# Controller.net
KiCad netlist of a schematic drawn in Altium Designer
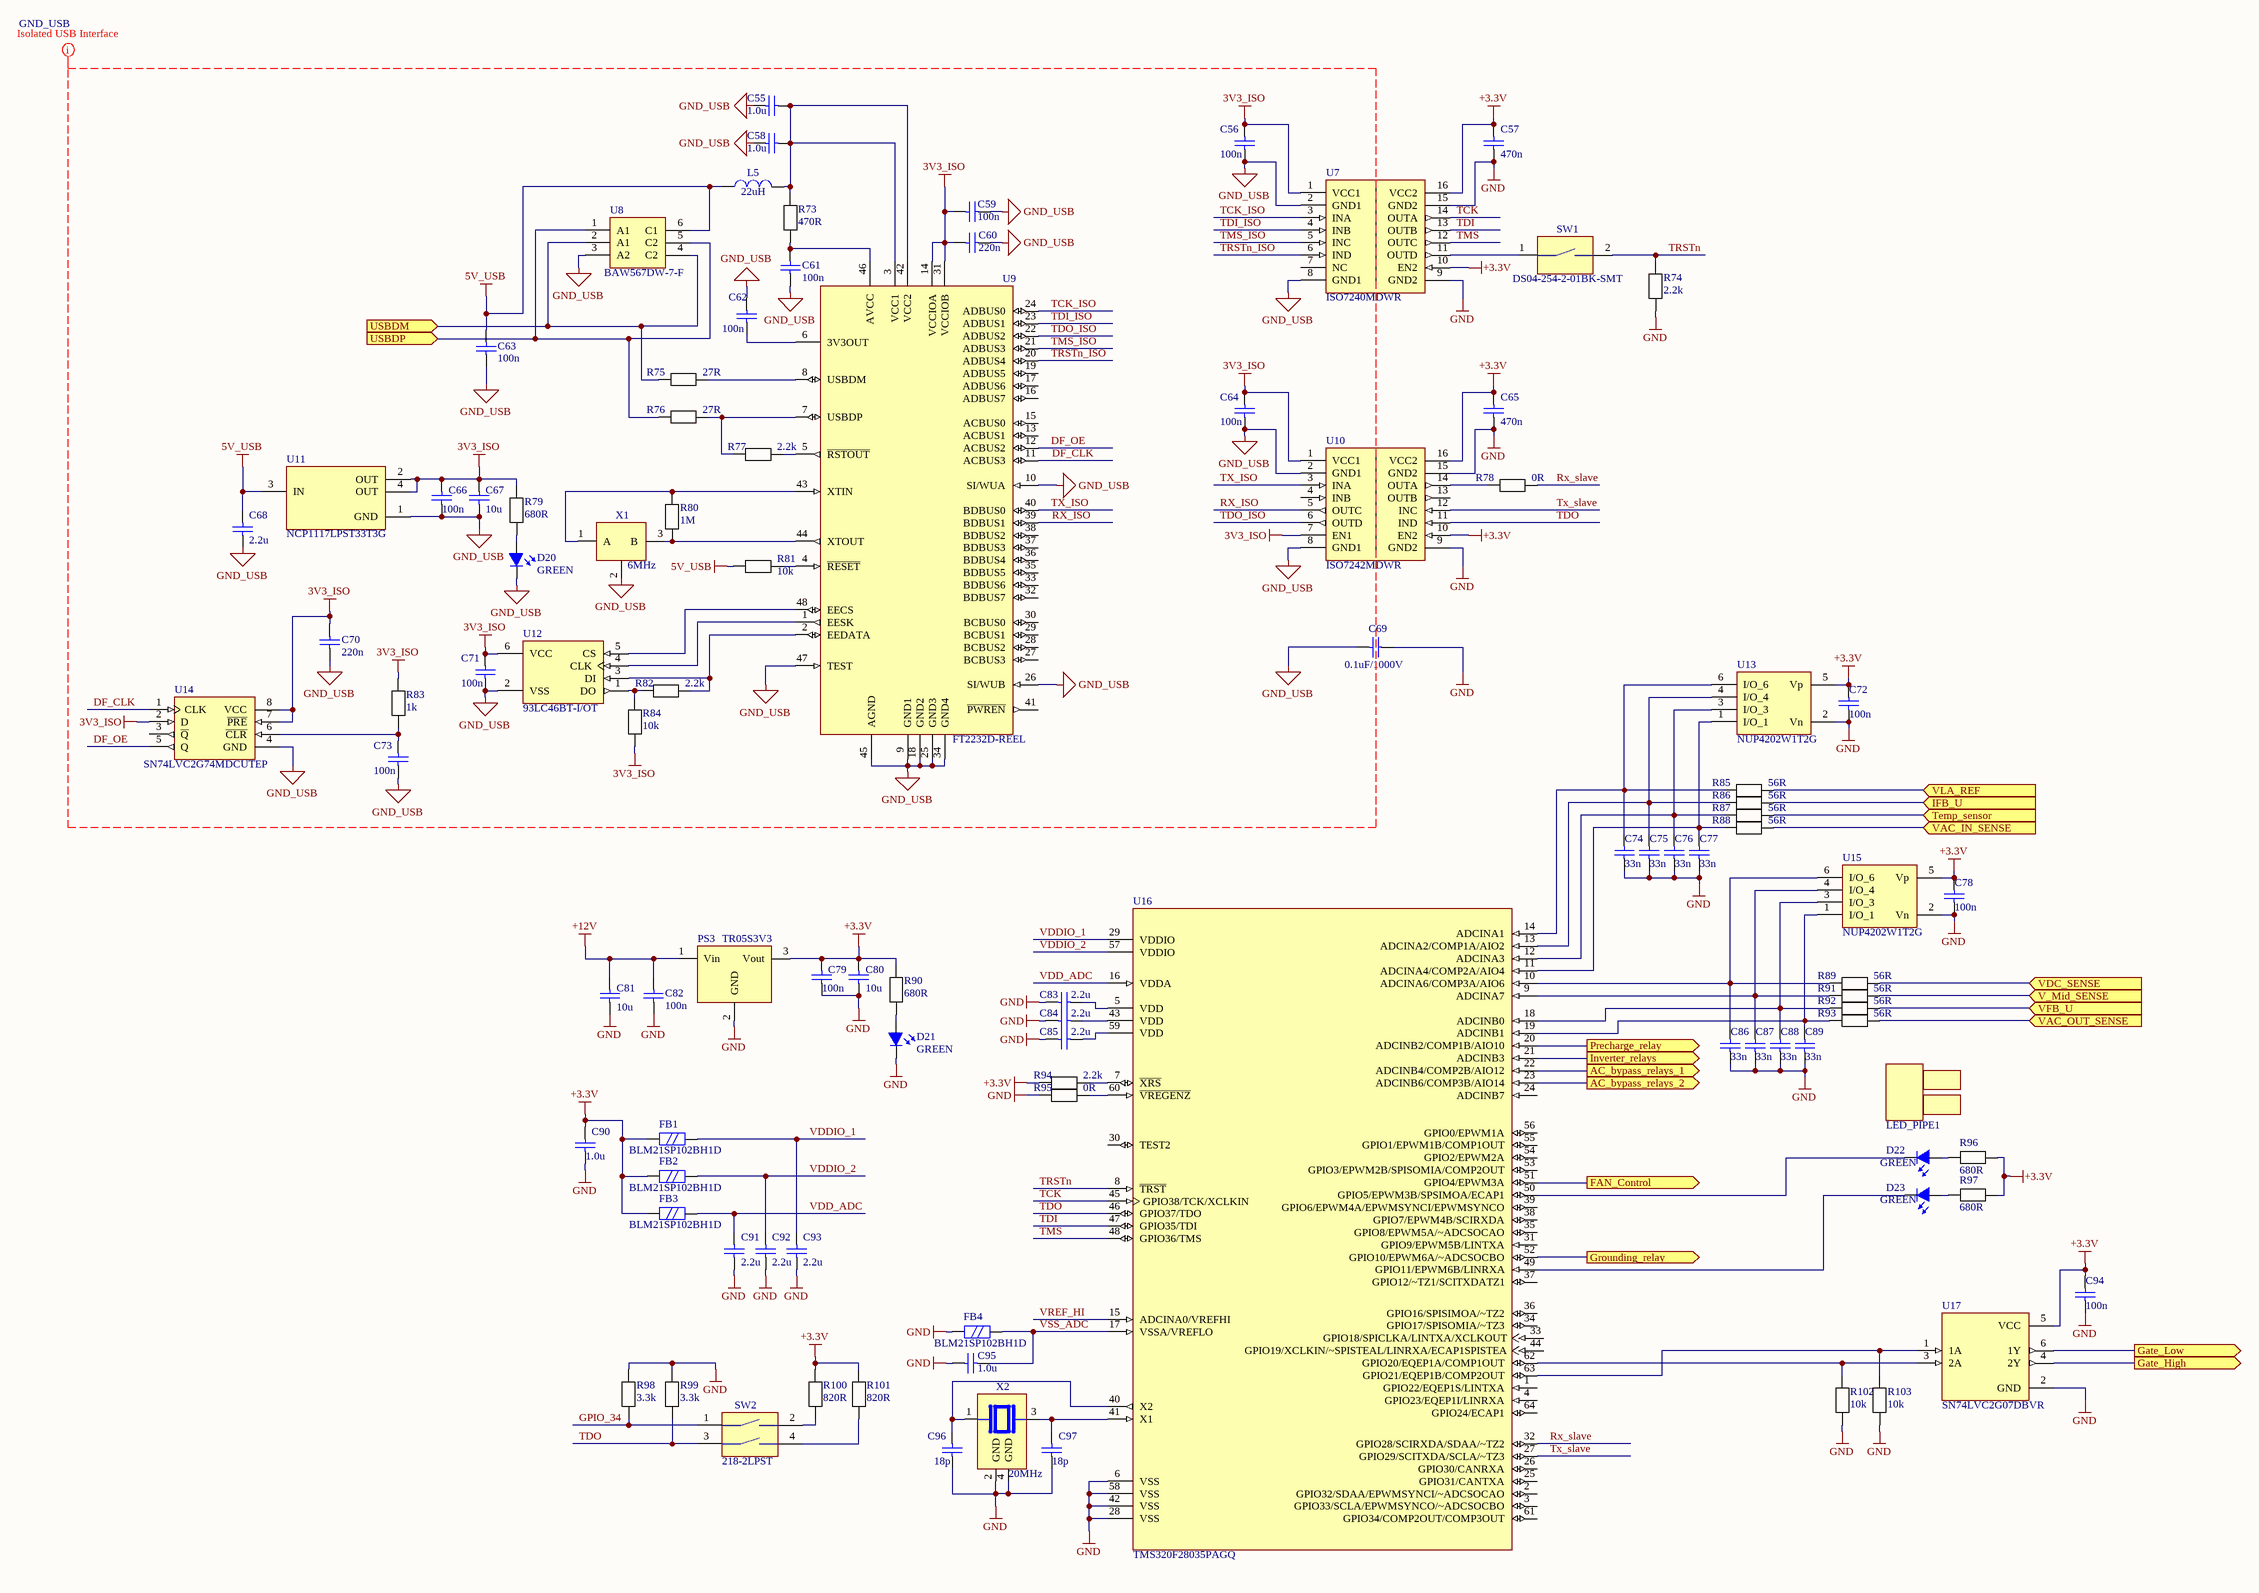
[diagram p0: Controller.SchDoc]

(export (version "E")
  (design (tool "Eeschema 10.0.6"))
  (components
    (comp (ref "C55")
      (value "1.0u")
      (footprint "C0603")
      (description "Capacitor 1.0u 0603 +-10% 50V")
      (fields (field (name "PART NUMBER") "CAP_YAG_CC0603KRX7R9BB105_X7R") (field (name "MFR") "Yageo"))
      (libsource (lib "Cap_Yag_0603_X7R_50_10%$") (part "CAP_YAG_CC0603KRX7R9BB105_X7R"))
    )
    (comp (ref "C56")
      (value "100n")
      (footprint "C0603")
      (description "Capacitor 100n 0603 +-10% 50V")
      (fields
        (field (name "PART NUMBER") "CAP_YAG_CC0603KRX7R9BB104_X7R")
        (field (name "MPN") "CC0603KRX7R9BB104")
      )
      (libsource (lib "Cap_Yag_0603_X7R_50_10%$") (part "CAP_YAG_CC0603KRX7R9BB104_X7R"))
    )
    (comp (ref "C57")
      (value "470n")
      (footprint "C0603")
      (description "Capacitor 470n 0603 +-10% 50V")
      (fields (field (name "PART NUMBER") "CAP_YAG_CC0603KRX7R9BB474_X7R") (field (name "MFR") "Yageo"))
      (libsource (lib "Cap_Yag_0603_X7R_50_10%$") (part "CAP_YAG_CC0603KRX7R9BB474_X7R"))
    )
    (comp (ref "C58")
      (value "1.0u")
      (footprint "C0603")
      (description "Capacitor 1.0u 0603 +-10% 50V")
      (fields (field (name "PART NUMBER") "CAP_YAG_CC0603KRX7R9BB105_X7R") (field (name "MFR") "Yageo"))
      (libsource (lib "Cap_Yag_0603_X7R_50_10%$") (part "CAP_YAG_CC0603KRX7R9BB105_X7R"))
    )
    (comp (ref "C59")
      (value "100n")
      (footprint "C0603")
      (description "Capacitor 100n 0603 +-10% 50V")
      (fields
        (field (name "PART NUMBER") "CAP_YAG_CC0603KRX7R9BB104_X7R")
        (field (name "MPN") "CC0603KRX7R9BB104")
      )
      (libsource (lib "Cap_Yag_0603_X7R_50_10%$") (part "CAP_YAG_CC0603KRX7R9BB104_X7R"))
    )
    (comp (ref "C60")
      (value "220n")
      (footprint "C0603")
      (description "Capacitor 220n 0603 +-10% 50V")
      (fields (field (name "PART NUMBER") "CAP_YAG_CC0603KRX7R9BB224_X7R") (field (name "MFR") "Yageo"))
      (libsource (lib "Cap_Yag_0603_X7R_50_10%$") (part "CAP_YAG_CC0603KRX7R9BB224_X7R"))
    )
    (comp (ref "C61")
      (value "100n")
      (footprint "C0603")
      (description "Capacitor 100n 0603 +-10% 50V")
      (fields
        (field (name "PART NUMBER") "CAP_YAG_CC0603KRX7R9BB104_X7R")
        (field (name "MPN") "CC0603KRX7R9BB104")
      )
      (libsource (lib "Cap_Yag_0603_X7R_50_10%$") (part "CAP_YAG_CC0603KRX7R9BB104_X7R"))
    )
    (comp (ref "C62")
      (value "100n")
      (footprint "C0603")
      (description "Capacitor 100n 0603 +-10% 50V")
      (fields
        (field (name "PART NUMBER") "CAP_YAG_CC0603KRX7R9BB104_X7R")
        (field (name "MPN") "CC0603KRX7R9BB104")
      )
      (libsource (lib "Cap_Yag_0603_X7R_50_10%$") (part "CAP_YAG_CC0603KRX7R9BB104_X7R"))
    )
    (comp (ref "C63")
      (value "100n")
      (footprint "C0603")
      (description "Capacitor 100n 0603 +-10% 50V")
      (fields
        (field (name "PART NUMBER") "CAP_YAG_CC0603KRX7R9BB104_X7R")
        (field (name "MANUFACTURER PART NUMBER") "CC0603KRX7R9BB104")
      )
      (libsource (lib "Cap_Yag_0603_X7R_50_10%$") (part "CAP_YAG_CC0603KRX7R9BB104_X7R"))
    )
    (comp (ref "C64")
      (value "100n")
      (footprint "C0603")
      (description "Capacitor 100n 0603 +-10% 50V")
      (fields
        (field (name "PART NUMBER") "CAP_YAG_CC0603KRX7R9BB104_X7R")
        (field (name "MPN") "CC0603KRX7R9BB104")
      )
      (libsource (lib "Cap_Yag_0603_X7R_50_10%$") (part "CAP_YAG_CC0603KRX7R9BB104_X7R"))
    )
    (comp (ref "C65")
      (value "470n")
      (footprint "C0603")
      (description "Capacitor 470n 0603 +-10% 50V")
      (fields (field (name "PART NUMBER") "CAP_YAG_CC0603KRX7R9BB474_X7R") (field (name "MFR") "Yageo"))
      (libsource (lib "Cap_Yag_0603_X7R_50_10%$") (part "CAP_YAG_CC0603KRX7R9BB474_X7R"))
    )
    (comp (ref "C66")
      (value "100n")
      (footprint "C0603")
      (description "Capacitor 100n 0603 +-10% 50V")
      (fields
        (field (name "PART NUMBER") "CAP_YAG_CC0603KRX7R9BB104_X7R")
        (field (name "MPN") "CC0603KRX7R9BB104")
      )
      (libsource (lib "Cap_Yag_0603_X7R_50_10%$") (part "CAP_YAG_CC0603KRX7R9BB104_X7R"))
    )
    (comp (ref "C67")
      (value "10u")
      (footprint "C1206")
      (description "Capacitor 10u 1206 +-10% 25V")
      (fields (field (name "MFR") "Yageo") (field (name "MPN") "CC1206KKX7R8BB106"))
      (libsource (lib "Inverter_2kW") (part "CAP_YAG_CC1206KKX7R8BB106"))
    )
    (comp (ref "C68")
      (value "2.2u")
      (footprint "C0603")
      (description "Capacitor 2.2u 0603 +-10% 25V")
      (fields (field (name "PART NUMBER") "CAP_YAG_CC0603KRX5R8BB225_X5R") (field (name "MFR") "Yageo"))
      (libsource (lib "Cap_Yag_0603_X5R_25_10%$") (part "CAP_YAG_CC0603KRX5R8BB225_X5R"))
    )
    (comp (ref "C69")
      (value "0.1uF/1000V")
      (footprint "C1812")
      (description "0.1uF ±10% 1000V")
      (fields (field (name "MPN") "C1812C104KDRACTU") (field (name "MFR") "KEMET"))
      (libsource (lib "RCL") (part "CAP"))
    )
    (comp (ref "C70")
      (value "220n")
      (footprint "C0603")
      (description "Capacitor 220n 0603 +-10% 50V")
      (fields (field (name "PART NUMBER") "CAP_YAG_CC0603KRX7R9BB224_X7R") (field (name "MFR") "Yageo"))
      (libsource (lib "Cap_Yag_0603_X7R_50_10%$") (part "CAP_YAG_CC0603KRX7R9BB224_X7R"))
    )
    (comp (ref "C71")
      (value "100n")
      (footprint "C0603")
      (description "Capacitor 100n 0603 +-10% 50V")
      (fields
        (field (name "PART NUMBER") "CAP_YAG_CC0603KRX7R9BB104_X7R")
        (field (name "MPN") "CC0603KRX7R9BB104")
      )
      (libsource (lib "Cap_Yag_0603_X7R_50_10%$") (part "CAP_YAG_CC0603KRX7R9BB104_X7R"))
    )
    (comp (ref "C72")
      (value "100n")
      (footprint "C0603")
      (description "Capacitor 100n 0603 +-10% 50V")
      (fields
        (field (name "PART NUMBER") "CAP_YAG_CC0603KRX7R9BB104_X7R")
        (field (name "MPN") "CC0603KRX7R9BB104")
      )
      (libsource (lib "Cap_Yag_0603_X7R_50_10%$") (part "CAP_YAG_CC0603KRX7R9BB104_X7R"))
    )
    (comp (ref "C73")
      (value "100n")
      (footprint "C0603")
      (description "Capacitor 100n 0603 +-10% 50V")
      (fields
        (field (name "PART NUMBER") "CAP_YAG_CC0603KRX7R9BB104_X7R")
        (field (name "MPN") "CC0603KRX7R9BB104")
      )
      (libsource (lib "Cap_Yag_0603_X7R_50_10%$") (part "CAP_YAG_CC0603KRX7R9BB104_X7R"))
    )
    (comp (ref "C74")
      (value "33n")
      (footprint "C0603")
      (description "Capacitor 33n 0603 +-10% 50V")
      (fields (field (name "PART NUMBER") "CAP_YAG_CC0603KRX7R9BB333_X7R") (field (name "MFR") "Yageo"))
      (libsource (lib "Cap_Yag_0603_X7R_50_10%$") (part "CAP_YAG_CC0603KRX7R9BB333_X7R"))
    )
    (comp (ref "C75")
      (value "33n")
      (footprint "C0603")
      (description "Capacitor 33n 0603 +-10% 50V")
      (fields (field (name "PART NUMBER") "CAP_YAG_CC0603KRX7R9BB333_X7R") (field (name "MFR") "Yageo"))
      (libsource (lib "Cap_Yag_0603_X7R_50_10%$") (part "CAP_YAG_CC0603KRX7R9BB333_X7R"))
    )
    (comp (ref "C76")
      (value "33n")
      (footprint "C0603")
      (description "Capacitor 33n 0603 +-10% 50V")
      (fields (field (name "PART NUMBER") "CAP_YAG_CC0603KRX7R9BB333_X7R") (field (name "MFR") "Yageo"))
      (libsource (lib "Cap_Yag_0603_X7R_50_10%$") (part "CAP_YAG_CC0603KRX7R9BB333_X7R"))
    )
    (comp (ref "C77")
      (value "33n")
      (footprint "C0603")
      (description "Capacitor 33n 0603 +-10% 50V")
      (fields (field (name "PART NUMBER") "CAP_YAG_CC0603KRX7R9BB333_X7R") (field (name "MFR") "Yageo"))
      (libsource (lib "Cap_Yag_0603_X7R_50_10%$") (part "CAP_YAG_CC0603KRX7R9BB333_X7R"))
    )
    (comp (ref "C78")
      (value "100n")
      (footprint "C0603")
      (description "Capacitor 100n 0603 +-10% 50V")
      (fields
        (field (name "PART NUMBER") "CAP_YAG_CC0603KRX7R9BB104_X7R")
        (field (name "MPN") "CC0603KRX7R9BB104")
      )
      (libsource (lib "Cap_Yag_0603_X7R_50_10%$") (part "CAP_YAG_CC0603KRX7R9BB104_X7R"))
    )
    (comp (ref "C79")
      (value "100n")
      (footprint "C0603")
      (description "Capacitor 100n 0603 +-10% 50V")
      (fields
        (field (name "PART NUMBER") "CAP_YAG_CC0603KRX7R9BB104_X7R")
        (field (name "MPN") "CC0603KRX7R9BB104")
      )
      (libsource (lib "Cap_Yag_0603_X7R_50_10%$") (part "CAP_YAG_CC0603KRX7R9BB104_X7R"))
    )
    (comp (ref "C80")
      (value "10u")
      (footprint "C1206")
      (description "Capacitor 10u 1206 +-10% 25V")
      (fields (field (name "MFR") "Yageo") (field (name "MPN") "CC1206KKX7R8BB106"))
      (libsource (lib "Inverter_2kW") (part "CAP_YAG_CC1206KKX7R8BB106"))
    )
    (comp (ref "C81")
      (value "10u")
      (footprint "C1206")
      (description "Capacitor 10u 1206 +-10% 25V")
      (fields (field (name "MFR") "Yageo") (field (name "MPN") "CC1206KKX7R8BB106"))
      (libsource (lib "Inverter_2kW") (part "CAP_YAG_CC1206KKX7R8BB106"))
    )
    (comp (ref "C82")
      (value "100n")
      (footprint "C0603")
      (description "Capacitor 100n 0603 +-10% 50V")
      (fields
        (field (name "PART NUMBER") "CAP_YAG_CC0603KRX7R9BB104_X7R")
        (field (name "MANUFACTURER PART NUMBER") "CC0603KRX7R9BB104")
      )
      (libsource (lib "Cap_Yag_0603_X7R_50_10%$") (part "CAP_YAG_CC0603KRX7R9BB104_X7R"))
    )
    (comp (ref "C83")
      (value "2.2u")
      (footprint "C0603")
      (description "Capacitor 2.2u 0603 +-10% 25V")
      (fields (field (name "PART NUMBER") "CAP_YAG_CC0603KRX5R8BB225_X5R") (field (name "MFR") "Yageo"))
      (libsource (lib "Cap_Yag_0603_X5R_25_10%$") (part "CAP_YAG_CC0603KRX5R8BB225_X5R"))
    )
    (comp (ref "C84")
      (value "2.2u")
      (footprint "C0603")
      (description "Capacitor 2.2u 0603 +-10% 25V")
      (fields (field (name "PART NUMBER") "CAP_YAG_CC0603KRX5R8BB225_X5R") (field (name "MFR") "Yageo"))
      (libsource (lib "Cap_Yag_0603_X5R_25_10%$") (part "CAP_YAG_CC0603KRX5R8BB225_X5R"))
    )
    (comp (ref "C85")
      (value "2.2u")
      (footprint "C0603")
      (description "Capacitor 2.2u 0603 +-10% 25V")
      (fields (field (name "PART NUMBER") "CAP_YAG_CC0603KRX5R8BB225_X5R") (field (name "MFR") "Yageo"))
      (libsource (lib "Cap_Yag_0603_X5R_25_10%$") (part "CAP_YAG_CC0603KRX5R8BB225_X5R"))
    )
    (comp (ref "C86")
      (value "33n")
      (footprint "C0603")
      (description "Capacitor 33n 0603 +-10% 50V")
      (fields (field (name "PART NUMBER") "CAP_YAG_CC0603KRX7R9BB333_X7R") (field (name "MFR") "Yageo"))
      (libsource (lib "Cap_Yag_0603_X7R_50_10%$") (part "CAP_YAG_CC0603KRX7R9BB333_X7R"))
    )
    (comp (ref "C87")
      (value "33n")
      (footprint "C0603")
      (description "Capacitor 33n 0603 +-10% 50V")
      (fields (field (name "PART NUMBER") "CAP_YAG_CC0603KRX7R9BB333_X7R") (field (name "MFR") "Yageo"))
      (libsource (lib "Cap_Yag_0603_X7R_50_10%$") (part "CAP_YAG_CC0603KRX7R9BB333_X7R"))
    )
    (comp (ref "C88")
      (value "33n")
      (footprint "C0603")
      (description "Capacitor 33n 0603 +-10% 50V")
      (fields (field (name "PART NUMBER") "CAP_YAG_CC0603KRX7R9BB333_X7R") (field (name "MFR") "Yageo"))
      (libsource (lib "Cap_Yag_0603_X7R_50_10%$") (part "CAP_YAG_CC0603KRX7R9BB333_X7R"))
    )
    (comp (ref "C89")
      (value "33n")
      (footprint "C0603")
      (description "Capacitor 33n 0603 +-10% 50V")
      (fields (field (name "PART NUMBER") "CAP_YAG_CC0603KRX7R9BB333_X7R") (field (name "MFR") "Yageo"))
      (libsource (lib "Cap_Yag_0603_X7R_50_10%$") (part "CAP_YAG_CC0603KRX7R9BB333_X7R"))
    )
    (comp (ref "C90")
      (value "1.0u")
      (footprint "C0603")
      (description "Capacitor 1.0u 0603 +-10% 25V")
      (fields (field (name "PART NUMBER") "CAP_YAG_CC0603KRX5R8BB105_X5R") (field (name "MFR") "Yageo"))
      (libsource (lib "Cap_Yag_0603_X5R_25_10%$") (part "CAP_YAG_CC0603KRX5R8BB105_X5R"))
    )
    (comp (ref "C91")
      (value "2.2u")
      (footprint "C0603")
      (description "Capacitor 2.2u 0603 +-10% 25V")
      (fields (field (name "PART NUMBER") "CAP_YAG_CC0603KRX5R8BB225_X5R") (field (name "MFR") "Yageo"))
      (libsource (lib "Cap_Yag_0603_X5R_25_10%$") (part "CAP_YAG_CC0603KRX5R8BB225_X5R"))
    )
    (comp (ref "C92")
      (value "2.2u")
      (footprint "C0603")
      (description "Capacitor 2.2u 0603 +-10% 25V")
      (fields (field (name "PART NUMBER") "CAP_YAG_CC0603KRX5R8BB225_X5R") (field (name "MFR") "Yageo"))
      (libsource (lib "Cap_Yag_0603_X5R_25_10%$") (part "CAP_YAG_CC0603KRX5R8BB225_X5R"))
    )
    (comp (ref "C93")
      (value "2.2u")
      (footprint "C0603")
      (description "Capacitor 2.2u 0603 +-10% 25V")
      (fields (field (name "PART NUMBER") "CAP_YAG_CC0603KRX5R8BB225_X5R") (field (name "MFR") "Yageo"))
      (libsource (lib "Cap_Yag_0603_X5R_25_10%$") (part "CAP_YAG_CC0603KRX5R8BB225_X5R"))
    )
    (comp (ref "C94")
      (value "100n")
      (footprint "C0603")
      (description "Capacitor 100n 0603 +-10% 50V")
      (fields
        (field (name "PART NUMBER") "CAP_YAG_CC0603KRX7R9BB104_X7R")
        (field (name "MPN") "CC0603KRX7R9BB104")
      )
      (libsource (lib "Cap_Yag_0603_X7R_50_10%$") (part "CAP_YAG_CC0603KRX7R9BB104_X7R"))
    )
    (comp (ref "C95")
      (value "1.0u")
      (footprint "C0603")
      (description "Capacitor 1.0u 0603 +-10% 25V")
      (fields (field (name "PART NUMBER") "CAP_YAG_CC0603KRX5R8BB105_X5R") (field (name "MFR") "Yageo"))
      (libsource (lib "Cap_Yag_0603_X5R_25_10%$") (part "CAP_YAG_CC0603KRX5R8BB105_X5R"))
    )
    (comp (ref "C96")
      (value "18p")
      (footprint "C0603")
      (description "Capacitor 18p 0603 +-10% 50V")
      (fields (field (name "PART NUMBER") "CAP_YAG_CC0603KRNPO9BN180_NPO") (field (name "MFR") "Yageo"))
      (libsource (lib "Cap_Yag_0603_NPO_50_10%$") (part "CAP_YAG_CC0603KRNPO9BN180_NPO"))
    )
    (comp (ref "C97")
      (value "18p")
      (footprint "C0603")
      (description "Capacitor 18p 0603 +-10% 50V")
      (fields (field (name "PART NUMBER") "CAP_YAG_CC0603KRNPO9BN180_NPO") (field (name "MFR") "Yageo"))
      (libsource (lib "Cap_Yag_0603_NPO_50_10%$") (part "CAP_YAG_CC0603KRNPO9BN180_NPO"))
    )
    (comp (ref "D20")
      (value "GREEN")
      (footprint "LED0805")
      (description "SMD Surface Mount LED, 5 mA")
      (fields (field (name "MPN") "VCDG1112H-4BY3C-TR") (field (name "MFR") "Stanley Electric"))
      (libsource (lib "Inverter_2kW") (part "LED_SMD"))
    )
    (comp (ref "D21")
      (value "GREEN")
      (footprint "LED0805")
      (description "SMD Surface Mount LED, 5 mA")
      (fields (field (name "MPN") "VCDG1112H-4BY3C-TR") (field (name "MFR") "Stanley Electric"))
      (libsource (lib "Inverter_2kW") (part "LED_SMD"))
    )
    (comp (ref "D22")
      (value "GREEN")
      (footprint "LED0805")
      (description "SMD Surface Mount LED, 5 mA")
      (fields (field (name "MPN") "VCDG1112H-4BY3C-TR") (field (name "MFR") "Stanley Electric"))
      (libsource (lib "Inverter_2kW") (part "LED_SMD"))
    )
    (comp (ref "D23")
      (value "GREEN")
      (footprint "LED0805")
      (description "SMD Surface Mount LED, 5 mA")
      (fields (field (name "MPN") "VCDG1112H-4BY3C-TR") (field (name "MFR") "Stanley Electric"))
      (libsource (lib "Inverter_2kW") (part "LED_SMD"))
    )
    (comp (ref "FB1")
      (value "BLM21SP102BH1D")
      (footprint "R0805")
      (description "FERRITE BEAD 1 KOHM 0805 1LN")
      (fields (field (name "MFR") "Murata Electronics"))
      (libsource (lib "SchematicLib") (part "SMD_FB"))
    )
    (comp (ref "FB2")
      (value "BLM21SP102BH1D")
      (footprint "R0805")
      (description "FERRITE BEAD 1 KOHM 0805 1LN")
      (fields (field (name "MFR") "Murata Electronics"))
      (libsource (lib "SchematicLib") (part "SMD_FB"))
    )
    (comp (ref "FB3")
      (value "BLM21SP102BH1D")
      (footprint "R0805")
      (description "FERRITE BEAD 1 KOHM 0805 1LN")
      (fields (field (name "MFR") "Murata Electronics"))
      (libsource (lib "SchematicLib") (part "SMD_FB"))
    )
    (comp (ref "FB4")
      (value "BLM21SP102BH1D")
      (footprint "R0805")
      (description "FERRITE BEAD 1 KOHM 0805 1LN")
      (fields (field (name "MFR") "Murata Electronics"))
      (libsource (lib "SchematicLib") (part "SMD_FB"))
    )
    (comp (ref "L5")
      (value "22uH")
      (footprint "IND_NRH3012T")
      (description "Power Inductors - SMD 3012 22uH 756mOhms +/-20%Tol 500mA")
      (fields (field (name "MPN") "NRH3012T220MN") (field (name "MFR") "Taiyo Yuden"))
      (libsource (lib "WirelessCharger") (part "Inductor"))
    )
    (comp (ref "LED_PIPE1")
      (value "RLP2-400-800")
      (footprint "RLP2-400-800")
      (description "LED Light Pipes SMD Double RA 2.8mm 20mm Protrusion")
      (fields (field (name "MFR") "Bivar"))
      (libsource (lib "Inverter_2kW") (part "RLP2-400-800"))
    )
    (comp (ref "PS3")
      (value "TR05S3V3")
      (footprint "TR05S3V3")
      (description "Non-Isolated DC/DC Converters DC-DC CONV, SWITCHING REG, 0.5A")
      (fields (field (name "MFR") "XP Power"))
      (libsource (lib "Inverter_2kW") (part "TR05S3V3"))
    )
    (comp (ref "R73")
      (value "470R")
      (footprint "R0603")
      (description "0.1W/ 470ohm±1%")
      (fields (field (name "MPN") "RC0603FR-0470RL") (field (name "MFR") "Yageo"))
      (libsource (lib "RCL") (part "RES"))
    )
    (comp (ref "R74")
      (value "2.2k")
      (footprint "R0603")
      (description "0.1W/ 2.2kohm±1%")
      (fields (field (name "MPN") "RC0603FR-072K2L") (field (name "MFR") "Yageo"))
      (libsource (lib "RCL") (part "RES"))
    )
    (comp (ref "R75")
      (value "27R")
      (footprint "R0603")
      (description "0.1W/ 27ohm±1%")
      (fields (field (name "MPN") "RC0603FR-027RL") (field (name "MFR") "Yageo"))
      (libsource (lib "RCL") (part "RES"))
    )
    (comp (ref "R76")
      (value "27R")
      (footprint "R0603")
      (description "0.1W/ 27ohm±1%")
      (fields (field (name "MPN") "RC0603FR-027RL") (field (name "MFR") "Yageo"))
      (libsource (lib "RCL") (part "RES"))
    )
    (comp (ref "R77")
      (value "2.2k")
      (footprint "R0603")
      (description "0.1W/ 2.2kohm±1%")
      (fields (field (name "MPN") "RC0603FR-072K2L") (field (name "MFR") "Yageo"))
      (libsource (lib "RCL") (part "RES"))
    )
    (comp (ref "R78")
      (value "0R")
      (footprint "R0603")
      (description "0.1W/ 0ohm±1%")
      (fields (field (name "MPN") "RC0603FR-070RL") (field (name "MFR") "Yageo"))
      (libsource (lib "RCL") (part "RES"))
    )
    (comp (ref "R79")
      (value "680R")
      (footprint "R0603")
      (description "0.1W/ 680ohm±1%")
      (fields (field (name "MPN") "RC0603FR-0680RL") (field (name "MFR") "Yageo"))
      (libsource (lib "RCL") (part "RES"))
    )
    (comp (ref "R80")
      (value "1M")
      (footprint "R0603")
      (description "0.1W/ 1Mohm±1%")
      (fields (field (name "MPN") "RC0603FR-071ML") (field (name "MFR") "Yageo"))
      (libsource (lib "RCL") (part "RES"))
    )
    (comp (ref "R81")
      (value "10k")
      (footprint "R0603")
      (description "0.1W/ 10kohm±1%")
      (fields (field (name "MPN") "RC0603FR-0710KL") (field (name "MFR") "Yageo"))
      (libsource (lib "RCL") (part "RES"))
    )
    (comp (ref "R82")
      (value "2.2k")
      (footprint "R0603")
      (description "0.1W/ 2.2kohm±1%")
      (fields (field (name "MPN") "RC0603FR-072K2L") (field (name "MFR") "Yageo"))
      (libsource (lib "RCL") (part "RES"))
    )
    (comp (ref "R83")
      (value "1k")
      (footprint "R0603")
      (description "0.1W/ 1kohm±1%")
      (fields (field (name "MPN") "RC0603FR-071KL") (field (name "MFR") "Yageo"))
      (libsource (lib "RCL") (part "RES"))
    )
    (comp (ref "R84")
      (value "10k")
      (footprint "R0603")
      (description "0.1W/ 10kohm±1%")
      (fields (field (name "MPN") "RC0603FR-0710KL") (field (name "MFR") "Yageo"))
      (libsource (lib "RCL") (part "RES"))
    )
    (comp (ref "R85")
      (value "56R")
      (footprint "R0603")
      (description "0.1W/ 56ohm±1%")
      (fields (field (name "MPN") "RC0603FR-056RL") (field (name "MFR") "Yageo"))
      (libsource (lib "RCL") (part "RES"))
    )
    (comp (ref "R86")
      (value "56R")
      (footprint "R0603")
      (description "0.1W/ 56ohm±1%")
      (fields (field (name "MPN") "RC0603FR-056RL") (field (name "MFR") "Yageo"))
      (libsource (lib "RCL") (part "RES"))
    )
    (comp (ref "R87")
      (value "56R")
      (footprint "R0603")
      (description "0.1W/ 56ohm±1%")
      (fields (field (name "MPN") "RC0603FR-056RL") (field (name "MFR") "Yageo"))
      (libsource (lib "RCL") (part "RES"))
    )
    (comp (ref "R88")
      (value "56R")
      (footprint "R0603")
      (description "0.1W/ 56ohm±1%")
      (fields (field (name "MPN") "RC0603FR-056RL") (field (name "MFR") "Yageo"))
      (libsource (lib "RCL") (part "RES"))
    )
    (comp (ref "R89")
      (value "56R")
      (footprint "R0603")
      (description "0.1W/ 56ohm±1%")
      (fields (field (name "MPN") "RC0603FR-056RL") (field (name "MFR") "Yageo"))
      (libsource (lib "RCL") (part "RES"))
    )
    (comp (ref "R90")
      (value "680R")
      (footprint "R0603")
      (description "0.1W/ 680ohm±1%")
      (fields (field (name "MPN") "RC0603FR-0680RL") (field (name "MFR") "Yageo"))
      (libsource (lib "RCL") (part "RES"))
    )
    (comp (ref "R91")
      (value "56R")
      (footprint "R0603")
      (description "0.1W/ 56ohm±1%")
      (fields (field (name "MPN") "RC0603FR-056RL") (field (name "MFR") "Yageo"))
      (libsource (lib "RCL") (part "RES"))
    )
    (comp (ref "R92")
      (value "56R")
      (footprint "R0603")
      (description "0.1W/ 56ohm±1%")
      (fields (field (name "MPN") "RC0603FR-056RL") (field (name "MFR") "Yageo"))
      (libsource (lib "RCL") (part "RES"))
    )
    (comp (ref "R93")
      (value "56R")
      (footprint "R0603")
      (description "0.1W/ 56ohm±1%")
      (fields (field (name "MPN") "RC0603FR-056RL") (field (name "MFR") "Yageo"))
      (libsource (lib "RCL") (part "RES"))
    )
    (comp (ref "R94")
      (value "2.2k")
      (footprint "R0603")
      (description "0.1W/ 2.2kohm±1%")
      (fields (field (name "MPN") "RC0603FR-072K2L") (field (name "MFR") "Yageo"))
      (libsource (lib "RCL") (part "RES"))
    )
    (comp (ref "R95")
      (value "0R")
      (footprint "R0603")
      (description "0.1W/ 0ohm±1%")
      (fields (field (name "MPN") "RC0603FR-070RL") (field (name "MFR") "Yageo"))
      (libsource (lib "RCL") (part "RES"))
    )
    (comp (ref "R96")
      (value "680R")
      (footprint "R0603")
      (description "0.1W/ 680ohm±1%")
      (fields (field (name "MPN") "RC0603FR-0680RL") (field (name "MFR") "Yageo"))
      (libsource (lib "RCL") (part "RES"))
    )
    (comp (ref "R97")
      (value "680R")
      (footprint "R0603")
      (description "0.1W/ 680ohm±1%")
      (fields (field (name "MPN") "RC0603FR-0680RL") (field (name "MFR") "Yageo"))
      (libsource (lib "RCL") (part "RES"))
    )
    (comp (ref "R98")
      (value "3.3k")
      (footprint "R0603")
      (description "0.1W/ 3.3kohm±1%")
      (fields (field (name "MPN") "RC0603FR-073K3L") (field (name "MFR") "Yageo"))
      (libsource (lib "RCL") (part "RES"))
    )
    (comp (ref "R99")
      (value "3.3k")
      (footprint "R0603")
      (description "0.1W/ 3.3kohm±1%")
      (fields (field (name "MPN") "RC0603FR-073K3L") (field (name "MFR") "Yageo"))
      (libsource (lib "RCL") (part "RES"))
    )
    (comp (ref "R100")
      (value "820R")
      (footprint "R0603")
      (description "0.1W/ 820ohm±1%")
      (fields (field (name "MPN") "RC0603FR-0820RL") (field (name "MFR") "Yageo"))
      (libsource (lib "RCL") (part "RES"))
    )
    (comp (ref "R101")
      (value "820R")
      (footprint "R0603")
      (description "0.1W/ 820ohm±1%")
      (fields (field (name "MPN") "RC0603FR-0820RL") (field (name "MFR") "Yageo"))
      (libsource (lib "RCL") (part "RES"))
    )
    (comp (ref "R102")
      (value "10k")
      (footprint "R0603")
      (description "0.1W/ 10kohm±1%")
      (fields (field (name "MPN") "RC0603FR-0710KL") (field (name "MFR") "Yageo"))
      (libsource (lib "RCL") (part "RES"))
    )
    (comp (ref "R103")
      (value "10k")
      (footprint "R0603")
      (description "0.1W/ 10kohm±1%")
      (fields (field (name "MPN") "RC0603FR-0710KL") (field (name "MFR") "Yageo"))
      (libsource (lib "RCL") (part "RES"))
    )
    (comp (ref "SW1")
      (value "DS04-254-2-01BK-SMT")
      (footprint "SW_DS04-254-2-01BK-SMT")
      (description "DIP Switches/SIP Switches 1 12 Positions, Surface Mount, 2.54 mm Pitch, Slide Actuator, DIP Switch")
      (fields (field (name "MFR") "CUI Devices"))
      (libsource (lib "Inverter_2kW") (part "1POS_DIPSW"))
    )
    (comp (ref "SW2")
      (value "218-2LPST")
      (footprint "218-2LPST")
      (description "DIP Switches/SIP Switches SPST 2 switch sections")
      (fields (field (name "MFR") "CTS Electronic Components"))
      (libsource (lib "Inverter_2kW") (part "218-2LPST"))
    )
    (comp (ref "U7")
      (value "ISO7240MDWR")
      (footprint "SOIC127P1030X265-16N")
      (description "Digital Isolators Quad Ch 4/0 150Mbps Digi Iso")
      (fields (field (name "MFR") "Texas Instruments"))
      (libsource (lib "Inverter_2kW") (part "ISO7240MDWR"))
    )
    (comp (ref "U8")
      (value "BAW567DW-7-F")
      (footprint "SOT65P210X110-6N")
      (description "Diodes - General Purpose, Power, Switching 75V 200mW")
      (fields (field (name "MFR") "Microchip"))
      (libsource (lib "Inverter_2kW") (part "BAW567DW-7-F"))
    )
    (comp (ref "U9")
      (value "FT2232D-REEL")
      (footprint "LQFP48")
      (description "USB Bridge, USB to UART USB 2.0 UART Interface 48-LQFP _7x7_")
      (fields (field (name "MFR") "FTDI, Future"))
      (libsource (lib "Inverter_2kW") (part "FT2232D"))
    )
    (comp (ref "U10")
      (value "ISO7242MDWR")
      (footprint "SOIC127P1030X265-16N")
      (description "Digital Isolators Quad Ch 2/2 150Mbps Dig Iso")
      (fields (field (name "MFR") "Texas Instruments"))
      (libsource (lib "Inverter_2kW") (part "ISO7242MDWR"))
    )
    (comp (ref "U11")
      (value "NCP1117LPST33T3G")
      (footprint "SOT223R")
      (description "LDO Voltage Regulators LOW DROPOUT REGULATORS")
      (fields (field (name "MFR") "onsemi"))
      (libsource (lib "EnergyMeter") (part "LD1117S33TR"))
    )
    (comp (ref "U12")
      (value "93LC46BT-I/OT")
      (footprint "SOT95P280X145-6N")
      (description "EEPROM Memory IC 1Kb _64 x 16_ SPI 2MHz SOT-23-6")
      (fields (field (name "MFR") "Microchip"))
      (libsource (lib "Inverter_2kW") (part "93LC46BT-I/OT"))
    )
    (comp (ref "U13")
      (value "NUP4202W1T2G")
      (footprint "SOT65P210X110-6N")
      (description "ESD Suppressors / TVS Diodes LOW CAP DIODE TVS ARRAY")
      (fields (field (name "MFR") "onsemi"))
      (libsource (lib "Inverter_2kW") (part "NUP4202W1T2G"))
    )
    (comp (ref "U14")
      (value "SN74LVC2G74MDCUTEP")
      (footprint "SOP50P310X90-8N")
      (description "Flip-Flops Sgl Pos Edge Trgrd D-Type Flip-Flop")
      (fields (field (name "MFR") "Texas Instruments"))
      (libsource (lib "Inverter_2kW") (part "SN74LVC2G74MDCUTEP"))
    )
    (comp (ref "U15")
      (value "NUP4202W1T2G")
      (footprint "SOT65P210X110-6N")
      (description "ESD Suppressors / TVS Diodes LOW CAP DIODE TVS ARRAY")
      (fields (field (name "MFR") "onsemi"))
      (libsource (lib "Inverter_2kW") (part "NUP4202W1T2G"))
    )
    (comp (ref "U16")
      (value "TMS320F28035PAGQ")
      (footprint "QFP50P1200X1200X120-64N")
      (description "32-bit Microcontrollers - MCU Piccolo Microcntrlr")
      (fields (field (name "MFR") "Texas Instruments"))
      (libsource (lib "Inverter_2kW") (part "TMS320F28035PAGQ"))
    )
    (comp (ref "U17")
      (value "SN74LVC2G07DBVR")
      (footprint "SOT95P280X145-6N")
      (description "Dual Buffer/Driver with Open-Drain Output 6-SOT-23 -40 to 125")
      (fields (field (name "MFR") "Texas Instruments"))
      (libsource (lib "Inverter_2kW") (part "SN74LVC2G07DBVR"))
    )
    (comp (ref "X1")
      (value "6MHz")
      (footprint "OSC_CSTCR6M00G53-R0")
      (description "Resonators 6.0 MHZ")
      (fields (field (name "MPN") "CSTCR6M00G53-R0") (field (name "MFR") "Murata"))
      (libsource (lib "Inverter_2kW") (part "XTAL"))
    )
    (comp (ref "X2")
      (value "20MHz")
      (footprint "XTAL_AMB8")
      (description "Crystals CRYSTAL 20.0000MHZ 10PF SMD")
      (fields (field (name "MPN") "ABM8-20.000MHZ-10-B1U-T") (field (name "MFR") "ABRACON"))
      (libsource (lib "Inverter_2kW") (part "ABM8-20.000MHZ"))
    )
  )
  (nets
    (net (code "1") (name "+3.3V") (class "Default")
      (node (ref "C57") (pin "2") (pinfunction "2_2") (pintype "passive"))
      (node (ref "C65") (pin "2") (pinfunction "2_2") (pintype "passive"))
      (node (ref "C72") (pin "2") (pinfunction "2_2") (pintype "passive"))
      (node (ref "C78") (pin "2") (pinfunction "2_2") (pintype "passive"))
      (node (ref "C79") (pin "2") (pinfunction "2_2") (pintype "passive"))
      (node (ref "C80") (pin "2") (pinfunction "2_2") (pintype "passive"))
      (node (ref "C90") (pin "2") (pinfunction "2_2") (pintype "passive"))
      (node (ref "C94") (pin "2") (pinfunction "2_2") (pintype "passive"))
      (node (ref "FB1") (pin "2") (pinfunction "2_2") (pintype "passive"))
      (node (ref "FB2") (pin "2") (pinfunction "2_2") (pintype "passive"))
      (node (ref "FB3") (pin "2") (pinfunction "2_2") (pintype "passive"))
      (node (ref "PS3") (pin "3") (pinfunction "Vout_3") (pintype "passive"))
      (node (ref "R100") (pin "2") (pinfunction "2_2") (pintype "passive"))
      (node (ref "R101") (pin "2") (pinfunction "2_2") (pintype "passive"))
      (node (ref "R90") (pin "2") (pinfunction "2_2") (pintype "passive"))
      (node (ref "R94") (pin "1") (pinfunction "1_1") (pintype "passive"))
      (node (ref "R96") (pin "2") (pinfunction "2_2") (pintype "passive"))
      (node (ref "R97") (pin "2") (pinfunction "2_2") (pintype "passive"))
      (node (ref "U10") (pin "10") (pinfunction "EN2_10") (pintype "input"))
      (node (ref "U10") (pin "16") (pinfunction "VCC2_16") (pintype "power_in"))
      (node (ref "U13") (pin "5") (pinfunction "Vp_5") (pintype "power_in"))
      (node (ref "U15") (pin "5") (pinfunction "Vp_5") (pintype "power_in"))
      (node (ref "U17") (pin "5") (pinfunction "VCC_5") (pintype "power_in"))
      (node (ref "U7") (pin "10") (pinfunction "EN2_10") (pintype "input"))
      (node (ref "U7") (pin "16") (pinfunction "VCC2_16") (pintype "power_in"))
    )
    (net (code "2") (name "+12V") (class "Default")
      (node (ref "C81") (pin "2") (pinfunction "2_2") (pintype "passive"))
      (node (ref "C82") (pin "2") (pinfunction "2_2") (pintype "passive"))
      (node (ref "PS3") (pin "1") (pinfunction "Vin_1") (pintype "passive"))
    )
    (net (code "3") (name "/AC_bypass_relays_1") (class "Default")
      (node (ref "U16") (pin "22") (pinfunction "ADCINB4/COMP2B/AIO12_22") (pintype "input"))
    )
    (net (code "4") (name "/AC_bypass_relays_2") (class "Default")
      (node (ref "U16") (pin "23") (pinfunction "ADCINB6/COMP3B/AIO14_23") (pintype "input"))
    )
    (net (code "5") (name "/DF_CLK") (class "Default")
      (node (ref "U14") (pin "1") (pinfunction "CLK_1") (pintype "input"))
      (node (ref "U9") (pin "11") (pinfunction "ACBUS3_11") (pintype "bidirectional"))
    )
    (net (code "6") (name "/DF_OE") (class "Default")
      (node (ref "U14") (pin "5") (pinfunction "Q_5") (pintype "output"))
      (node (ref "U9") (pin "12") (pinfunction "ACBUS2_12") (pintype "bidirectional"))
    )
    (net (code "7") (name "/FAN_Control") (class "Default")
      (node (ref "U16") (pin "51") (pinfunction "GPIO4/EPWM3A_51") (pintype "bidirectional"))
    )
    (net (code "8") (name "/GPIO_34") (class "Default")
      (node (ref "R98") (pin "1") (pinfunction "1_1") (pintype "passive"))
      (node (ref "SW2") (pin "1") (pinfunction "1_1") (pintype "passive"))
    )
    (net (code "9") (name "/Gate_High") (class "Default")
      (node (ref "U17") (pin "4") (pinfunction "2Y_4") (pintype "output"))
    )
    (net (code "10") (name "/Gate_Low") (class "Default")
      (node (ref "U17") (pin "6") (pinfunction "1Y_6") (pintype "output"))
    )
    (net (code "11") (name "/Grounding_relay") (class "Default")
      (node (ref "U16") (pin "52") (pinfunction "GPIO10/EPWM6A/~ADCSOCBO_52") (pintype "bidirectional"))
    )
    (net (code "12") (name "/IFB_U") (class "Default")
      (node (ref "R86") (pin "1") (pinfunction "1_1") (pintype "passive"))
    )
    (net (code "13") (name "/Inverter_relays") (class "Default")
      (node (ref "U16") (pin "21") (pinfunction "ADCINB3_21") (pintype "input"))
    )
    (net (code "14") (name "/Precharge_relay") (class "Default")
      (node (ref "U16") (pin "20") (pinfunction "ADCINB2/COMP1B/AIO10_20") (pintype "input"))
    )
    (net (code "15") (name "/RX_ISO") (class "Default")
      (node (ref "U10") (pin "5") (pinfunction "OUTC_5") (pintype "output"))
      (node (ref "U9") (pin "39") (pinfunction "BDBUS1_39") (pintype "bidirectional"))
    )
    (net (code "16") (name "/Rx_slave") (class "Default")
      (node (ref "R78") (pin "2") (pinfunction "2_2") (pintype "passive"))
      (node (ref "U16") (pin "32") (pinfunction "GPIO28/SCIRXDA/SDAA/~TZ2_32") (pintype "bidirectional"))
    )
    (net (code "17") (name "/TCK") (class "Default")
      (node (ref "U16") (pin "45") (pinfunction "GPIO38/TCK/XCLKIN_45") (pintype "input"))
      (node (ref "U7") (pin "14") (pinfunction "OUTA_14") (pintype "output"))
    )
    (net (code "18") (name "/TCK_ISO") (class "Default")
      (node (ref "U7") (pin "3") (pinfunction "INA_3") (pintype "input"))
      (node (ref "U9") (pin "24") (pinfunction "ADBUS0_24") (pintype "bidirectional"))
    )
    (net (code "19") (name "/TDI") (class "Default")
      (node (ref "U16") (pin "47") (pinfunction "GPIO35/TDI_47") (pintype "bidirectional"))
      (node (ref "U7") (pin "13") (pinfunction "OUTB_13") (pintype "output"))
    )
    (net (code "20") (name "/TDI_ISO") (class "Default")
      (node (ref "U7") (pin "4") (pinfunction "INB_4") (pintype "input"))
      (node (ref "U9") (pin "23") (pinfunction "ADBUS1_23") (pintype "bidirectional"))
    )
    (net (code "21") (name "/TDO") (class "Default")
      (node (ref "R99") (pin "1") (pinfunction "1_1") (pintype "passive"))
      (node (ref "SW2") (pin "3") (pinfunction "3_3") (pintype "passive"))
      (node (ref "U10") (pin "11") (pinfunction "IND_11") (pintype "input"))
      (node (ref "U16") (pin "46") (pinfunction "GPIO37/TDO_46") (pintype "bidirectional"))
    )
    (net (code "22") (name "/TDO_ISO") (class "Default")
      (node (ref "U10") (pin "6") (pinfunction "OUTD_6") (pintype "output"))
      (node (ref "U9") (pin "22") (pinfunction "ADBUS2_22") (pintype "bidirectional"))
    )
    (net (code "23") (name "/TMS") (class "Default")
      (node (ref "U16") (pin "48") (pinfunction "GPIO36/TMS_48") (pintype "bidirectional"))
      (node (ref "U7") (pin "12") (pinfunction "OUTC_12") (pintype "output"))
    )
    (net (code "24") (name "/TMS_ISO") (class "Default")
      (node (ref "U7") (pin "5") (pinfunction "INC_5") (pintype "input"))
      (node (ref "U9") (pin "21") (pinfunction "ADBUS3_21") (pintype "bidirectional"))
    )
    (net (code "25") (name "/TRSTn") (class "Default")
      (node (ref "R74") (pin "2") (pinfunction "2_2") (pintype "passive"))
      (node (ref "SW1") (pin "2") (pinfunction "2_2") (pintype "passive"))
      (node (ref "U16") (pin "8") (pinfunction "~{TRST}_8") (pintype "input"))
    )
    (net (code "26") (name "/TRSTn_ISO") (class "Default")
      (node (ref "U7") (pin "6") (pinfunction "IND_6") (pintype "input"))
      (node (ref "U9") (pin "20") (pinfunction "ADBUS4_20") (pintype "bidirectional"))
    )
    (net (code "27") (name "/TX_ISO") (class "Default")
      (node (ref "U10") (pin "3") (pinfunction "INA_3") (pintype "input"))
      (node (ref "U9") (pin "40") (pinfunction "BDBUS0_40") (pintype "bidirectional"))
    )
    (net (code "28") (name "/Temp_sensor") (class "Default")
      (node (ref "R87") (pin "1") (pinfunction "1_1") (pintype "passive"))
    )
    (net (code "29") (name "/Tx_slave") (class "Default")
      (node (ref "U10") (pin "12") (pinfunction "INC_12") (pintype "input"))
      (node (ref "U16") (pin "27") (pinfunction "GPIO29/SCITXDA/SCLA/~TZ3_27") (pintype "bidirectional"))
    )
    (net (code "30") (name "/USBDM") (class "Default")
      (node (ref "R75") (pin "2") (pinfunction "2_2") (pintype "passive"))
      (node (ref "U8") (pin "2") (pinfunction "A1_2") (pintype "passive"))
      (node (ref "U8") (pin "4") (pinfunction "C2_4") (pintype "passive"))
    )
    (net (code "31") (name "/USBDP") (class "Default")
      (node (ref "R76") (pin "2") (pinfunction "2_2") (pintype "passive"))
      (node (ref "U8") (pin "1") (pinfunction "A1_1") (pintype "passive"))
      (node (ref "U8") (pin "5") (pinfunction "C2_5") (pintype "passive"))
    )
    (net (code "32") (name "/VAC_IN_SENSE") (class "Default")
      (node (ref "R88") (pin "1") (pinfunction "1_1") (pintype "passive"))
    )
    (net (code "33") (name "/VAC_OUT_SENSE") (class "Default")
      (node (ref "R93") (pin "1") (pinfunction "1_1") (pintype "passive"))
    )
    (net (code "34") (name "/VDC_SENSE") (class "Default")
      (node (ref "R89") (pin "1") (pinfunction "1_1") (pintype "passive"))
    )
    (net (code "35") (name "/VDDIO_1") (class "Default")
      (node (ref "C93") (pin "2") (pinfunction "2_2") (pintype "passive"))
      (node (ref "FB1") (pin "1") (pinfunction "1_1") (pintype "passive"))
      (node (ref "U16") (pin "29") (pinfunction "VDDIO_29") (pintype "power_in"))
    )
    (net (code "36") (name "/VDDIO_2") (class "Default")
      (node (ref "C92") (pin "2") (pinfunction "2_2") (pintype "passive"))
      (node (ref "FB2") (pin "1") (pinfunction "1_1") (pintype "passive"))
      (node (ref "U16") (pin "57") (pinfunction "VDDIO_57") (pintype "power_in"))
    )
    (net (code "37") (name "/VDD_ADC") (class "Default")
      (node (ref "C91") (pin "2") (pinfunction "2_2") (pintype "passive"))
      (node (ref "FB3") (pin "1") (pinfunction "1_1") (pintype "passive"))
      (node (ref "U16") (pin "16") (pinfunction "VDDA_16") (pintype "input"))
    )
    (net (code "38") (name "/VFB_U") (class "Default")
      (node (ref "R92") (pin "1") (pinfunction "1_1") (pintype "passive"))
    )
    (net (code "39") (name "/VLA_REF") (class "Default")
      (node (ref "R85") (pin "1") (pinfunction "1_1") (pintype "passive"))
    )
    (net (code "40") (name "/VREF_HI") (class "Default")
      (node (ref "U16") (pin "15") (pinfunction "ADCINA0/VREFHI_15") (pintype "input"))
    )
    (net (code "41") (name "/VSS_ADC") (class "Default")
      (node (ref "C95") (pin "2") (pinfunction "2_2") (pintype "passive"))
      (node (ref "FB4") (pin "1") (pinfunction "1_1") (pintype "passive"))
      (node (ref "U16") (pin "17") (pinfunction "VSSA/VREFLO_17") (pintype "input"))
    )
    (net (code "42") (name "/V_Mid_SENSE") (class "Default")
      (node (ref "R91") (pin "1") (pinfunction "1_1") (pintype "passive"))
    )
    (net (code "43") (name "3V3_ISO") (class "Default")
      (node (ref "C56") (pin "2") (pinfunction "2_2") (pintype "passive"))
      (node (ref "C59") (pin "2") (pinfunction "2_2") (pintype "passive"))
      (node (ref "C60") (pin "2") (pinfunction "2_2") (pintype "passive"))
      (node (ref "C64") (pin "2") (pinfunction "2_2") (pintype "passive"))
      (node (ref "C66") (pin "2") (pinfunction "2_2") (pintype "passive"))
      (node (ref "C67") (pin "2") (pinfunction "2_2") (pintype "passive"))
      (node (ref "C70") (pin "2") (pinfunction "2_2") (pintype "passive"))
      (node (ref "C71") (pin "2") (pinfunction "2_2") (pintype "passive"))
      (node (ref "R79") (pin "2") (pinfunction "2_2") (pintype "passive"))
      (node (ref "R83") (pin "2") (pinfunction "2_2") (pintype "passive"))
      (node (ref "R84") (pin "1") (pinfunction "1_1") (pintype "passive"))
      (node (ref "U10") (pin "1") (pinfunction "VCC1_1") (pintype "power_in"))
      (node (ref "U10") (pin "7") (pinfunction "EN1_7") (pintype "passive"))
      (node (ref "U11") (pin "2") (pinfunction "OUT_2") (pintype "power_in"))
      (node (ref "U11") (pin "4") (pinfunction "OUT_4") (pintype "power_in"))
      (node (ref "U12") (pin "6") (pinfunction "VCC_6") (pintype "power_in"))
      (node (ref "U14") (pin "2") (pinfunction "D_2") (pintype "input"))
      (node (ref "U14") (pin "7") (pinfunction "~{PRE}_7") (pintype "input"))
      (node (ref "U14") (pin "8") (pinfunction "VCC_8") (pintype "power_in"))
      (node (ref "U7") (pin "1") (pinfunction "VCC1_1") (pintype "power_in"))
      (node (ref "U9") (pin "14") (pinfunction "VCCIOA_14") (pintype "power_in"))
      (node (ref "U9") (pin "31") (pinfunction "VCCIOB_31") (pintype "power_in"))
    )
    (net (code "44") (name "5V_USB") (class "Default")
      (node (ref "C63") (pin "2") (pinfunction "2_2") (pintype "passive"))
      (node (ref "C68") (pin "2") (pinfunction "2_2") (pintype "passive"))
      (node (ref "L5") (pin "1") (pinfunction "1_1") (pintype "passive"))
      (node (ref "R81") (pin "1") (pinfunction "1_1") (pintype "passive"))
      (node (ref "U11") (pin "3") (pinfunction "IN_3") (pintype "power_in"))
      (node (ref "U8") (pin "6") (pinfunction "C1_6") (pintype "passive"))
    )
    (net (code "45") (name "GND") (class "Default")
      (node (ref "C57") (pin "1") (pinfunction "1_1") (pintype "passive"))
      (node (ref "C65") (pin "1") (pinfunction "1_1") (pintype "passive"))
      (node (ref "C69") (pin "1") (pinfunction "1_1") (pintype "passive"))
      (node (ref "C72") (pin "1") (pinfunction "1_1") (pintype "passive"))
      (node (ref "C74") (pin "1") (pinfunction "1_1") (pintype "passive"))
      (node (ref "C75") (pin "1") (pinfunction "1_1") (pintype "passive"))
      (node (ref "C76") (pin "1") (pinfunction "1_1") (pintype "passive"))
      (node (ref "C77") (pin "1") (pinfunction "1_1") (pintype "passive"))
      (node (ref "C78") (pin "1") (pinfunction "1_1") (pintype "passive"))
      (node (ref "C79") (pin "1") (pinfunction "1_1") (pintype "passive"))
      (node (ref "C80") (pin "1") (pinfunction "1_1") (pintype "passive"))
      (node (ref "C81") (pin "1") (pinfunction "1_1") (pintype "passive"))
      (node (ref "C82") (pin "1") (pinfunction "1_1") (pintype "passive"))
      (node (ref "C83") (pin "1") (pinfunction "1_1") (pintype "passive"))
      (node (ref "C84") (pin "1") (pinfunction "1_1") (pintype "passive"))
      (node (ref "C85") (pin "1") (pinfunction "1_1") (pintype "passive"))
      (node (ref "C86") (pin "1") (pinfunction "1_1") (pintype "passive"))
      (node (ref "C87") (pin "1") (pinfunction "1_1") (pintype "passive"))
      (node (ref "C88") (pin "1") (pinfunction "1_1") (pintype "passive"))
      (node (ref "C89") (pin "1") (pinfunction "1_1") (pintype "passive"))
      (node (ref "C90") (pin "1") (pinfunction "1_1") (pintype "passive"))
      (node (ref "C91") (pin "1") (pinfunction "1_1") (pintype "passive"))
      (node (ref "C92") (pin "1") (pinfunction "1_1") (pintype "passive"))
      (node (ref "C93") (pin "1") (pinfunction "1_1") (pintype "passive"))
      (node (ref "C94") (pin "1") (pinfunction "1_1") (pintype "passive"))
      (node (ref "C95") (pin "1") (pinfunction "1_1") (pintype "passive"))
      (node (ref "C96") (pin "1") (pinfunction "1_1") (pintype "passive"))
      (node (ref "C97") (pin "1") (pinfunction "1_1") (pintype "passive"))
      (node (ref "D21") (pin "C") (pinfunction "C_C") (pintype "passive"))
      (node (ref "FB4") (pin "2") (pinfunction "2_2") (pintype "passive"))
      (node (ref "PS3") (pin "2") (pinfunction "GND_2") (pintype "passive"))
      (node (ref "R102") (pin "1") (pinfunction "1_1") (pintype "passive"))
      (node (ref "R103") (pin "1") (pinfunction "1_1") (pintype "passive"))
      (node (ref "R74") (pin "1") (pinfunction "1_1") (pintype "passive"))
      (node (ref "R95") (pin "1") (pinfunction "1_1") (pintype "passive"))
      (node (ref "R98") (pin "2") (pinfunction "2_2") (pintype "passive"))
      (node (ref "R99") (pin "2") (pinfunction "2_2") (pintype "passive"))
      (node (ref "U10") (pin "15") (pinfunction "GND2_15") (pintype "power_in"))
      (node (ref "U10") (pin "9") (pinfunction "GND2_9") (pintype "power_in"))
      (node (ref "U13") (pin "2") (pinfunction "Vn_2") (pintype "power_in"))
      (node (ref "U15") (pin "2") (pinfunction "Vn_2") (pintype "power_in"))
      (node (ref "U16") (pin "28") (pinfunction "VSS_28") (pintype "power_in"))
      (node (ref "U16") (pin "42") (pinfunction "VSS_42") (pintype "power_in"))
      (node (ref "U16") (pin "58") (pinfunction "VSS_58") (pintype "power_in"))
      (node (ref "U16") (pin "6") (pinfunction "VSS_6") (pintype "power_in"))
      (node (ref "U17") (pin "2") (pinfunction "GND_2") (pintype "power_in"))
      (node (ref "U7") (pin "15") (pinfunction "GND2_15") (pintype "power_in"))
      (node (ref "U7") (pin "9") (pinfunction "GND2_9") (pintype "power_in"))
      (node (ref "X2") (pin "2") (pinfunction "GND_2") (pintype "power_in"))
      (node (ref "X2") (pin "4") (pinfunction "GND_4") (pintype "power_in"))
    )
    (net (code "46") (name "GND_USB") (class "Default")
      (node (ref "C55") (pin "1") (pinfunction "1_1") (pintype "passive"))
      (node (ref "C56") (pin "1") (pinfunction "1_1") (pintype "passive"))
      (node (ref "C58") (pin "1") (pinfunction "1_1") (pintype "passive"))
      (node (ref "C59") (pin "1") (pinfunction "1_1") (pintype "passive"))
      (node (ref "C60") (pin "1") (pinfunction "1_1") (pintype "passive"))
      (node (ref "C61") (pin "1") (pinfunction "1_1") (pintype "passive"))
      (node (ref "C62") (pin "1") (pinfunction "1_1") (pintype "passive"))
      (node (ref "C63") (pin "1") (pinfunction "1_1") (pintype "passive"))
      (node (ref "C64") (pin "1") (pinfunction "1_1") (pintype "passive"))
      (node (ref "C66") (pin "1") (pinfunction "1_1") (pintype "passive"))
      (node (ref "C67") (pin "1") (pinfunction "1_1") (pintype "passive"))
      (node (ref "C68") (pin "1") (pinfunction "1_1") (pintype "passive"))
      (node (ref "C69") (pin "2") (pinfunction "2_2") (pintype "passive"))
      (node (ref "C70") (pin "1") (pinfunction "1_1") (pintype "passive"))
      (node (ref "C71") (pin "1") (pinfunction "1_1") (pintype "passive"))
      (node (ref "C73") (pin "1") (pinfunction "1_1") (pintype "passive"))
      (node (ref "D20") (pin "C") (pinfunction "C_C") (pintype "passive"))
      (node (ref "U10") (pin "2") (pinfunction "GND1_2") (pintype "power_in"))
      (node (ref "U10") (pin "8") (pinfunction "GND1_8") (pintype "power_in"))
      (node (ref "U11") (pin "1") (pinfunction "GND_1") (pintype "power_in"))
      (node (ref "U12") (pin "2") (pinfunction "VSS_2") (pintype "power_in"))
      (node (ref "U14") (pin "4") (pinfunction "GND_4") (pintype "power_in"))
      (node (ref "U7") (pin "2") (pinfunction "GND1_2") (pintype "power_in"))
      (node (ref "U7") (pin "8") (pinfunction "GND1_8") (pintype "power_in"))
      (node (ref "U8") (pin "3") (pinfunction "A2_3") (pintype "passive"))
      (node (ref "U9") (pin "10") (pinfunction "SI/WUA_10") (pintype "input"))
      (node (ref "U9") (pin "18") (pinfunction "GND2_18") (pintype "power_in"))
      (node (ref "U9") (pin "25") (pinfunction "GND3_25") (pintype "power_in"))
      (node (ref "U9") (pin "26") (pinfunction "SI/WUB_26") (pintype "input"))
      (node (ref "U9") (pin "34") (pinfunction "GND4_34") (pintype "power_in"))
      (node (ref "U9") (pin "45") (pinfunction "AGND_45") (pintype "power_in"))
      (node (ref "U9") (pin "47") (pinfunction "TEST_47") (pintype "input"))
      (node (ref "U9") (pin "9") (pinfunction "GND1_9") (pintype "power_in"))
      (node (ref "X1") (pin "2") (pinfunction "GND_2") (pintype "passive"))
    )
    (net (code "47") (name "Net-(C83-Pad2)") (class "Default")
      (node (ref "C83") (pin "2") (pinfunction "2_2") (pintype "passive"))
      (node (ref "U16") (pin "5") (pinfunction "VDD_5") (pintype "power_in"))
    )
    (net (code "48") (name "Net-(C84-Pad2)") (class "Default")
      (node (ref "C84") (pin "2") (pinfunction "2_2") (pintype "passive"))
      (node (ref "U16") (pin "43") (pinfunction "VDD_43") (pintype "power_in"))
    )
    (net (code "49") (name "Net-(C85-Pad2)") (class "Default")
      (node (ref "C85") (pin "2") (pinfunction "2_2") (pintype "passive"))
      (node (ref "U16") (pin "59") (pinfunction "VDD_59") (pintype "power_in"))
    )
    (net (code "50") (name "Net-(D20-PadA)") (class "Default")
      (node (ref "D20") (pin "A") (pinfunction "A_A") (pintype "passive"))
      (node (ref "R79") (pin "1") (pinfunction "1_1") (pintype "passive"))
    )
    (net (code "51") (name "Net-(D21-PadA)") (class "Default")
      (node (ref "D21") (pin "A") (pinfunction "A_A") (pintype "passive"))
      (node (ref "R90") (pin "1") (pinfunction "1_1") (pintype "passive"))
    )
    (net (code "52") (name "Net-(D22-PadA)") (class "Default")
      (node (ref "D22") (pin "A") (pinfunction "A_A") (pintype "passive"))
      (node (ref "R96") (pin "1") (pinfunction "1_1") (pintype "passive"))
    )
    (net (code "53") (name "Net-(D23-PadA)") (class "Default")
      (node (ref "D23") (pin "A") (pinfunction "A_A") (pintype "passive"))
      (node (ref "R97") (pin "1") (pinfunction "1_1") (pintype "passive"))
    )
    (net (code "54") (name "Net-(R100-Pad1)") (class "Default")
      (node (ref "R100") (pin "1") (pinfunction "1_1") (pintype "passive"))
      (node (ref "SW2") (pin "2") (pinfunction "2_2") (pintype "passive"))
    )
    (net (code "55") (name "Net-(R101-Pad1)") (class "Default")
      (node (ref "R101") (pin "1") (pinfunction "1_1") (pintype "passive"))
      (node (ref "SW2") (pin "4") (pinfunction "4_4") (pintype "passive"))
    )
    (net (code "56") (name "Net-(U7-OUTD)") (class "Default")
      (node (ref "SW1") (pin "1") (pinfunction "1_1") (pintype "passive"))
      (node (ref "U7") (pin "11") (pinfunction "OUTD_11") (pintype "output"))
    )
    (net (code "57") (name "Net-(U9-3V3OUT)") (class "Default")
      (node (ref "C62") (pin "2") (pinfunction "2_2") (pintype "passive"))
      (node (ref "U9") (pin "6") (pinfunction "3V3OUT_6") (pintype "power_in"))
    )
    (net (code "58") (name "Net-(U9-AVCC)") (class "Default")
      (node (ref "C61") (pin "2") (pinfunction "2_2") (pintype "passive"))
      (node (ref "R73") (pin "2") (pinfunction "2_2") (pintype "passive"))
      (node (ref "U9") (pin "46") (pinfunction "AVCC_46") (pintype "power_in"))
    )
    (net (code "59") (name "Net-(U9-USBDM)") (class "Default")
      (node (ref "R75") (pin "1") (pinfunction "1_1") (pintype "passive"))
      (node (ref "U9") (pin "8") (pinfunction "USBDM_8") (pintype "bidirectional"))
    )
    (net (code "60") (name "Net-(U9-USBDP)") (class "Default")
      (node (ref "R76") (pin "1") (pinfunction "1_1") (pintype "passive"))
      (node (ref "R77") (pin "1") (pinfunction "1_1") (pintype "passive"))
      (node (ref "U9") (pin "7") (pinfunction "USBDP_7") (pintype "bidirectional"))
    )
    (net (code "61") (name "Net-(U9-VCC1)") (class "Default")
      (node (ref "C55") (pin "2") (pinfunction "2_2") (pintype "passive"))
      (node (ref "C58") (pin "2") (pinfunction "2_2") (pintype "passive"))
      (node (ref "L5") (pin "2") (pinfunction "2_2") (pintype "passive"))
      (node (ref "R73") (pin "1") (pinfunction "1_1") (pintype "passive"))
      (node (ref "U9") (pin "3") (pinfunction "VCC1_3") (pintype "power_in"))
      (node (ref "U9") (pin "42") (pinfunction "VCC2_42") (pintype "power_in"))
    )
    (net (code "62") (name "Net-(U9-XTIN)") (class "Default")
      (node (ref "R80") (pin "2") (pinfunction "2_2") (pintype "passive"))
      (node (ref "U9") (pin "43") (pinfunction "XTIN_43") (pintype "input"))
      (node (ref "X1") (pin "1") (pinfunction "A_1") (pintype "passive"))
    )
    (net (code "63") (name "Net-(U9-XTOUT)") (class "Default")
      (node (ref "R80") (pin "1") (pinfunction "1_1") (pintype "passive"))
      (node (ref "U9") (pin "44") (pinfunction "XTOUT_44") (pintype "output"))
      (node (ref "X1") (pin "3") (pinfunction "B_3") (pintype "passive"))
    )
    (net (code "64") (name "Net-(U9-~{RESET})") (class "Default")
      (node (ref "R81") (pin "2") (pinfunction "2_2") (pintype "passive"))
      (node (ref "U9") (pin "4") (pinfunction "~{RESET}_4") (pintype "input"))
    )
    (net (code "65") (name "Net-(U9-~{RSTOUT})") (class "Default")
      (node (ref "R77") (pin "2") (pinfunction "2_2") (pintype "passive"))
      (node (ref "U9") (pin "5") (pinfunction "~{RSTOUT}_5") (pintype "output"))
    )
    (net (code "66") (name "Net-(U10-OUTA)") (class "Default")
      (node (ref "R78") (pin "1") (pinfunction "1_1") (pintype "passive"))
      (node (ref "U10") (pin "14") (pinfunction "OUTA_14") (pintype "output"))
    )
    (net (code "67") (name "Net-(U12-CLK)") (class "Default")
      (node (ref "U12") (pin "4") (pinfunction "CLK_4") (pintype "input"))
      (node (ref "U9") (pin "1") (pinfunction "EESK_1") (pintype "output"))
    )
    (net (code "68") (name "Net-(U12-CS)") (class "Default")
      (node (ref "U12") (pin "5") (pinfunction "CS_5") (pintype "input"))
      (node (ref "U9") (pin "48") (pinfunction "EECS_48") (pintype "bidirectional"))
    )
    (net (code "69") (name "Net-(U12-DI)") (class "Default")
      (node (ref "R82") (pin "2") (pinfunction "2_2") (pintype "passive"))
      (node (ref "U12") (pin "3") (pinfunction "DI_3") (pintype "input"))
      (node (ref "U9") (pin "2") (pinfunction "EEDATA_2") (pintype "bidirectional"))
    )
    (net (code "70") (name "Net-(U12-DO)") (class "Default")
      (node (ref "R82") (pin "1") (pinfunction "1_1") (pintype "passive"))
      (node (ref "R84") (pin "2") (pinfunction "2_2") (pintype "passive"))
      (node (ref "U12") (pin "1") (pinfunction "DO_1") (pintype "output"))
    )
    (net (code "71") (name "Net-(U13-I{slash}O_1)") (class "Default")
      (node (ref "C77") (pin "2") (pinfunction "2_2") (pintype "passive"))
      (node (ref "R88") (pin "2") (pinfunction "2_2") (pintype "passive"))
      (node (ref "U13") (pin "1") (pinfunction "I/O_1_1") (pintype "passive"))
      (node (ref "U16") (pin "11") (pinfunction "ADCINA4/COMP2A/AIO4_11") (pintype "input"))
    )
    (net (code "72") (name "Net-(U13-I{slash}O_3)") (class "Default")
      (node (ref "C76") (pin "2") (pinfunction "2_2") (pintype "passive"))
      (node (ref "R87") (pin "2") (pinfunction "2_2") (pintype "passive"))
      (node (ref "U13") (pin "3") (pinfunction "I/O_3_3") (pintype "passive"))
      (node (ref "U16") (pin "12") (pinfunction "ADCINA3_12") (pintype "input"))
    )
    (net (code "73") (name "Net-(U13-I{slash}O_4)") (class "Default")
      (node (ref "C75") (pin "2") (pinfunction "2_2") (pintype "passive"))
      (node (ref "R86") (pin "2") (pinfunction "2_2") (pintype "passive"))
      (node (ref "U13") (pin "4") (pinfunction "I/O_4_4") (pintype "passive"))
      (node (ref "U16") (pin "13") (pinfunction "ADCINA2/COMP1A/AIO2_13") (pintype "input"))
    )
    (net (code "74") (name "Net-(U13-I{slash}O_6)") (class "Default")
      (node (ref "C74") (pin "2") (pinfunction "2_2") (pintype "passive"))
      (node (ref "R85") (pin "2") (pinfunction "2_2") (pintype "passive"))
      (node (ref "U13") (pin "6") (pinfunction "I/O_6_6") (pintype "passive"))
      (node (ref "U16") (pin "14") (pinfunction "ADCINA1_14") (pintype "input"))
    )
    (net (code "75") (name "Net-(U14-~{CLR})") (class "Default")
      (node (ref "C73") (pin "2") (pinfunction "2_2") (pintype "passive"))
      (node (ref "R83") (pin "1") (pinfunction "1_1") (pintype "passive"))
      (node (ref "U14") (pin "6") (pinfunction "~{CLR}_6") (pintype "input"))
    )
    (net (code "76") (name "Net-(U15-I{slash}O_1)") (class "Default")
      (node (ref "C89") (pin "2") (pinfunction "2_2") (pintype "passive"))
      (node (ref "R93") (pin "2") (pinfunction "2_2") (pintype "passive"))
      (node (ref "U15") (pin "1") (pinfunction "I/O_1_1") (pintype "passive"))
      (node (ref "U16") (pin "19") (pinfunction "ADCINB1_19") (pintype "input"))
    )
    (net (code "77") (name "Net-(U15-I{slash}O_3)") (class "Default")
      (node (ref "C88") (pin "2") (pinfunction "2_2") (pintype "passive"))
      (node (ref "R92") (pin "2") (pinfunction "2_2") (pintype "passive"))
      (node (ref "U15") (pin "3") (pinfunction "I/O_3_3") (pintype "passive"))
      (node (ref "U16") (pin "18") (pinfunction "ADCINB0_18") (pintype "input"))
    )
    (net (code "78") (name "Net-(U15-I{slash}O_4)") (class "Default")
      (node (ref "C87") (pin "2") (pinfunction "2_2") (pintype "passive"))
      (node (ref "R91") (pin "2") (pinfunction "2_2") (pintype "passive"))
      (node (ref "U15") (pin "4") (pinfunction "I/O_4_4") (pintype "passive"))
      (node (ref "U16") (pin "9") (pinfunction "ADCINA7_9") (pintype "input"))
    )
    (net (code "79") (name "Net-(U15-I{slash}O_6)") (class "Default")
      (node (ref "C86") (pin "2") (pinfunction "2_2") (pintype "passive"))
      (node (ref "R89") (pin "2") (pinfunction "2_2") (pintype "passive"))
      (node (ref "U15") (pin "6") (pinfunction "I/O_6_6") (pintype "passive"))
      (node (ref "U16") (pin "10") (pinfunction "ADCINA6/COMP3A/AIO6_10") (pintype "input"))
    )
    (net (code "80") (name "Net-(U16-GPIO5{slash}EPWM3B{slash}SPSIMOA{slash}ECAP1)") (class "Default")
      (node (ref "D22") (pin "C") (pinfunction "C_C") (pintype "passive"))
      (node (ref "U16") (pin "50") (pinfunction "GPIO5/EPWM3B/SPSIMOA/ECAP1_50") (pintype "bidirectional"))
    )
    (net (code "81") (name "Net-(U16-GPIO11{slash}EPWM6B{slash}LINRXA)") (class "Default")
      (node (ref "D23") (pin "C") (pinfunction "C_C") (pintype "passive"))
      (node (ref "U16") (pin "49") (pinfunction "GPIO11/EPWM6B/LINRXA_49") (pintype "input"))
    )
    (net (code "82") (name "Net-(U16-GPIO20{slash}EQEP1A{slash}COMP1OUT)") (class "Default")
      (node (ref "R102") (pin "2") (pinfunction "2_2") (pintype "passive"))
      (node (ref "U16") (pin "62") (pinfunction "GPIO20/EQEP1A/COMP1OUT_62") (pintype "bidirectional"))
      (node (ref "U17") (pin "3") (pinfunction "2A_3") (pintype "input"))
    )
    (net (code "83") (name "Net-(U16-GPIO21{slash}EQEP1B{slash}COMP2OUT)") (class "Default")
      (node (ref "R103") (pin "2") (pinfunction "2_2") (pintype "passive"))
      (node (ref "U16") (pin "63") (pinfunction "GPIO21/EQEP1B/COMP2OUT_63") (pintype "bidirectional"))
      (node (ref "U17") (pin "1") (pinfunction "1A_1") (pintype "input"))
    )
    (net (code "84") (name "Net-(U16-X1)") (class "Default")
      (node (ref "C97") (pin "2") (pinfunction "2_2") (pintype "passive"))
      (node (ref "U16") (pin "41") (pinfunction "X1_41") (pintype "input"))
      (node (ref "X2") (pin "3") (pinfunction "2_3") (pintype "passive"))
    )
    (net (code "85") (name "Net-(U16-X2)") (class "Default")
      (node (ref "C96") (pin "2") (pinfunction "2_2") (pintype "passive"))
      (node (ref "U16") (pin "40") (pinfunction "X2_40") (pintype "output"))
      (node (ref "X2") (pin "1") (pinfunction "1_1") (pintype "passive"))
    )
    (net (code "86") (name "Net-(U16-~{VREGENZ})") (class "Default")
      (node (ref "R95") (pin "2") (pinfunction "2_2") (pintype "passive"))
      (node (ref "U16") (pin "60") (pinfunction "~{VREGENZ}_60") (pintype "input"))
    )
    (net (code "87") (name "Net-(U16-~{XRS})") (class "Default")
      (node (ref "R94") (pin "2") (pinfunction "2_2") (pintype "passive"))
      (node (ref "U16") (pin "7") (pinfunction "~{XRS}_7") (pintype "bidirectional"))
    )
    (net (code "88") (name "unconnected-(U7-NC-Pad7)") (class "Default")
      (node (ref "U7") (pin "7") (pinfunction "NC_7") (pintype "passive"))
    )
    (net (code "89") (name "unconnected-(U9-ACBUS0-Pad15)") (class "Default")
      (node (ref "U9") (pin "15") (pinfunction "ACBUS0_15") (pintype "bidirectional"))
    )
    (net (code "90") (name "unconnected-(U9-ACBUS1-Pad13)") (class "Default")
      (node (ref "U9") (pin "13") (pinfunction "ACBUS1_13") (pintype "bidirectional"))
    )
    (net (code "91") (name "unconnected-(U9-ADBUS5-Pad19)") (class "Default")
      (node (ref "U9") (pin "19") (pinfunction "ADBUS5_19") (pintype "bidirectional"))
    )
    (net (code "92") (name "unconnected-(U9-ADBUS6-Pad17)") (class "Default")
      (node (ref "U9") (pin "17") (pinfunction "ADBUS6_17") (pintype "bidirectional"))
    )
    (net (code "93") (name "unconnected-(U9-ADBUS7-Pad16)") (class "Default")
      (node (ref "U9") (pin "16") (pinfunction "ADBUS7_16") (pintype "bidirectional"))
    )
    (net (code "94") (name "unconnected-(U9-BCBUS0-Pad30)") (class "Default")
      (node (ref "U9") (pin "30") (pinfunction "BCBUS0_30") (pintype "bidirectional"))
    )
    (net (code "95") (name "unconnected-(U9-BCBUS1-Pad29)") (class "Default")
      (node (ref "U9") (pin "29") (pinfunction "BCBUS1_29") (pintype "bidirectional"))
    )
    (net (code "96") (name "unconnected-(U9-BCBUS2-Pad28)") (class "Default")
      (node (ref "U9") (pin "28") (pinfunction "BCBUS2_28") (pintype "bidirectional"))
    )
    (net (code "97") (name "unconnected-(U9-BCBUS3-Pad27)") (class "Default")
      (node (ref "U9") (pin "27") (pinfunction "BCBUS3_27") (pintype "bidirectional"))
    )
    (net (code "98") (name "unconnected-(U9-BDBUS2-Pad38)") (class "Default")
      (node (ref "U9") (pin "38") (pinfunction "BDBUS2_38") (pintype "bidirectional"))
    )
    (net (code "99") (name "unconnected-(U9-BDBUS3-Pad37)") (class "Default")
      (node (ref "U9") (pin "37") (pinfunction "BDBUS3_37") (pintype "bidirectional"))
    )
    (net (code "100") (name "unconnected-(U9-BDBUS4-Pad36)") (class "Default")
      (node (ref "U9") (pin "36") (pinfunction "BDBUS4_36") (pintype "bidirectional"))
    )
    (net (code "101") (name "unconnected-(U9-BDBUS5-Pad35)") (class "Default")
      (node (ref "U9") (pin "35") (pinfunction "BDBUS5_35") (pintype "bidirectional"))
    )
    (net (code "102") (name "unconnected-(U9-BDBUS6-Pad33)") (class "Default")
      (node (ref "U9") (pin "33") (pinfunction "BDBUS6_33") (pintype "bidirectional"))
    )
    (net (code "103") (name "unconnected-(U9-BDBUS7-Pad32)") (class "Default")
      (node (ref "U9") (pin "32") (pinfunction "BDBUS7_32") (pintype "bidirectional"))
    )
    (net (code "104") (name "unconnected-(U9-~{PWREN}-Pad41)") (class "Default")
      (node (ref "U9") (pin "41") (pinfunction "~{PWREN}_41") (pintype "output"))
    )
    (net (code "105") (name "unconnected-(U10-INB-Pad4)") (class "Default")
      (node (ref "U10") (pin "4") (pinfunction "INB_4") (pintype "input"))
    )
    (net (code "106") (name "unconnected-(U10-OUTB-Pad13)") (class "Default")
      (node (ref "U10") (pin "13") (pinfunction "OUTB_13") (pintype "output"))
    )
    (net (code "107") (name "unconnected-(U14-~{Q}-Pad3)") (class "Default")
      (node (ref "U14") (pin "3") (pinfunction "~{Q}_3") (pintype "output"))
    )
    (net (code "108") (name "unconnected-(U16-ADCINB7-Pad24)") (class "Default")
      (node (ref "U16") (pin "24") (pinfunction "ADCINB7_24") (pintype "input"))
    )
    (net (code "109") (name "unconnected-(U16-GPIO0{slash}EPWM1A-Pad56)") (class "Default")
      (node (ref "U16") (pin "56") (pinfunction "GPIO0/EPWM1A_56") (pintype "bidirectional"))
    )
    (net (code "110") (name "unconnected-(U16-GPIO1{slash}EPWM1B{slash}COMP1OUT-Pad55)") (class "Default")
      (node (ref "U16") (pin "55") (pinfunction "GPIO1/EPWM1B/COMP1OUT_55") (pintype "bidirectional"))
    )
    (net (code "111") (name "unconnected-(U16-GPIO2{slash}EPWM2A-Pad54)") (class "Default")
      (node (ref "U16") (pin "54") (pinfunction "GPIO2/EPWM2A_54") (pintype "bidirectional"))
    )
    (net (code "112") (name "unconnected-(U16-GPIO3{slash}EPWM2B{slash}SPISOMIA{slash}COMP2OUT-Pad53)") (class "Default")
      (node (ref "U16") (pin "53") (pinfunction "GPIO3/EPWM2B/SPISOMIA/COMP2OUT_53") (pintype "bidirectional"))
    )
    (net (code "113") (name "unconnected-(U16-GPIO6{slash}EPWM4A{slash}EPWMSYNCI{slash}EPWMSYNCO-Pad39)") (class "Default")
      (node (ref "U16") (pin "39") (pinfunction "GPIO6/EPWM4A/EPWMSYNCI/EPWMSYNCO_39") (pintype "bidirectional"))
    )
    (net (code "114") (name "unconnected-(U16-GPIO7{slash}EPWM4B{slash}SCIRXDA-Pad38)") (class "Default")
      (node (ref "U16") (pin "38") (pinfunction "GPIO7/EPWM4B/SCIRXDA_38") (pintype "bidirectional"))
    )
    (net (code "115") (name "unconnected-(U16-GPIO8{slash}EPWM5A{slash}~ADCSOCAO-Pad35)") (class "Default")
      (node (ref "U16") (pin "35") (pinfunction "GPIO8/EPWM5A/~ADCSOCAO_35") (pintype "bidirectional"))
    )
    (net (code "116") (name "unconnected-(U16-GPIO9{slash}EPWM5B{slash}LINTXA-Pad31)") (class "Default")
      (node (ref "U16") (pin "31") (pinfunction "GPIO9/EPWM5B/LINTXA_31") (pintype "input"))
    )
    (net (code "117") (name "unconnected-(U16-GPIO12{slash}~TZ1{slash}SCITXDATZ1-Pad37)") (class "Default")
      (node (ref "U16") (pin "37") (pinfunction "GPIO12/~TZ1/SCITXDATZ1_37") (pintype "bidirectional"))
    )
    (net (code "118") (name "unconnected-(U16-GPIO16{slash}SPISIMOA{slash}~TZ2-Pad36)") (class "Default")
      (node (ref "U16") (pin "36") (pinfunction "GPIO16/SPISIMOA/~TZ2_36") (pintype "bidirectional"))
    )
    (net (code "119") (name "unconnected-(U16-GPIO17{slash}SPISOMIA{slash}~TZ3-Pad34)") (class "Default")
      (node (ref "U16") (pin "34") (pinfunction "GPIO17/SPISOMIA/~TZ3_34") (pintype "bidirectional"))
    )
    (net (code "120") (name "unconnected-(U16-GPIO18{slash}SPICLKA{slash}LINTXA{slash}XCLKOUT-Pad33)") (class "Default")
      (node (ref "U16") (pin "33") (pinfunction "GPIO18/SPICLKA/LINTXA/XCLKOUT_33") (pintype "input"))
    )
    (net (code "121") (name "unconnected-(U16-GPIO19{slash}XCLKIN{slash}~SPISTEAL{slash}LINRXA{slash}ECAP1SPISTEA-Pad44)") (class "Default")
      (node (ref "U16") (pin "44") (pinfunction "GPIO19/XCLKIN/~SPISTEAL/LINRXA/ECAP1SPISTEA_44") (pintype "input"))
    )
    (net (code "122") (name "unconnected-(U16-GPIO22{slash}EQEP1S{slash}LINTXA-Pad1)") (class "Default")
      (node (ref "U16") (pin "1") (pinfunction "GPIO22/EQEP1S/LINTXA_1") (pintype "input"))
    )
    (net (code "123") (name "unconnected-(U16-GPIO23{slash}EQEP1I{slash}LINRXA-Pad4)") (class "Default")
      (node (ref "U16") (pin "4") (pinfunction "GPIO23/EQEP1I/LINRXA_4") (pintype "input"))
    )
    (net (code "124") (name "unconnected-(U16-GPIO24{slash}ECAP1-Pad64)") (class "Default")
      (node (ref "U16") (pin "64") (pinfunction "GPIO24/ECAP1_64") (pintype "bidirectional"))
    )
    (net (code "125") (name "unconnected-(U16-GPIO30{slash}CANRXA-Pad26)") (class "Default")
      (node (ref "U16") (pin "26") (pinfunction "GPIO30/CANRXA_26") (pintype "bidirectional"))
    )
    (net (code "126") (name "unconnected-(U16-GPIO31{slash}CANTXA-Pad25)") (class "Default")
      (node (ref "U16") (pin "25") (pinfunction "GPIO31/CANTXA_25") (pintype "bidirectional"))
    )
    (net (code "127") (name "unconnected-(U16-GPIO32{slash}SDAA{slash}EPWMSYNCI{slash}~ADCSOCAO-Pad2)") (class "Default")
      (node (ref "U16") (pin "2") (pinfunction "GPIO32/SDAA/EPWMSYNCI/~ADCSOCAO_2") (pintype "bidirectional"))
    )
    (net (code "128") (name "unconnected-(U16-GPIO33{slash}SCLA{slash}EPWMSYNCO{slash}~ADCSOCBO-Pad3)") (class "Default")
      (node (ref "U16") (pin "3") (pinfunction "GPIO33/SCLA/EPWMSYNCO/~ADCSOCBO_3") (pintype "bidirectional"))
    )
    (net (code "129") (name "unconnected-(U16-GPIO34{slash}COMP2OUT{slash}COMP3OUT-Pad61)") (class "Default")
      (node (ref "U16") (pin "61") (pinfunction "GPIO34/COMP2OUT/COMP3OUT_61") (pintype "bidirectional"))
    )
    (net (code "130") (name "unconnected-(U16-TEST2-Pad30)") (class "Default")
      (node (ref "U16") (pin "30") (pinfunction "TEST2_30") (pintype "bidirectional"))
    )
  )
)
